# attiny85_jig.net
KiCad netlist of a schematic drawn in EAGLE
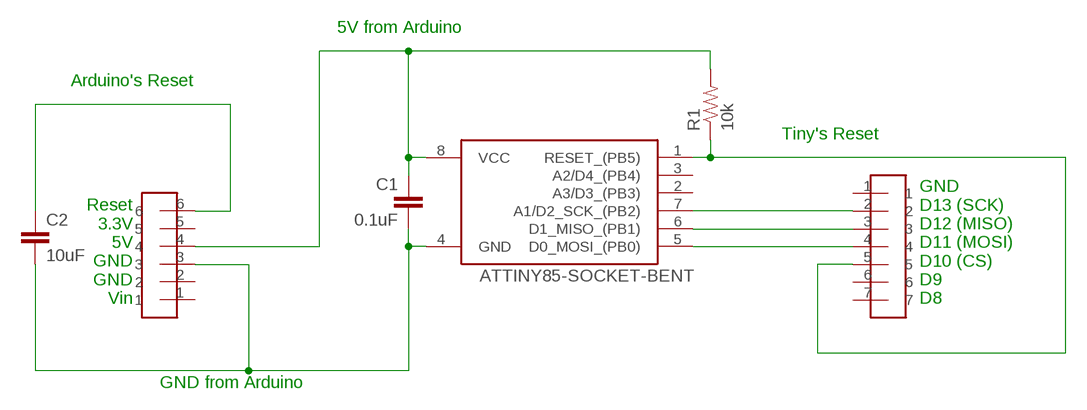
[diagram p0: schematic, sheet 1]

(export (version "E")
  (design (tool "Eeschema 10.0.6"))
  (components
    (comp (ref "C1")
      (value "0.1uF")
      (footprint "eagle-import:0805")
      (libsource (lib "eagle-import") (part "CAP-0805"))
    )
    (comp (ref "C2")
      (value "10uF")
      (footprint "eagle-import:0805")
      (libsource (lib "eagle-import") (part "CAP-0805"))
    )
    (comp (ref "R1")
      (value "10k")
      (footprint "eagle-import:0805")
      (libsource (lib "eagle-import") (part "RESISTOR-0805"))
    )
    (comp (ref "U$1")
      (value "ATTINY85-SOCKET-BENT")
      (footprint "eagle-import:SOCKET-8PIN-BENT")
      (libsource (lib "eagle-import") (part "ATTINY85-SOCKET-BENT"))
    )
    (comp (ref "U$2")
      (value "HEADER-6")
      (footprint "eagle-import:HEADER-6")
      (libsource (lib "eagle-import") (part "HEADER-6"))
    )
    (comp (ref "U$3")
      (value "HEADER-7")
      (footprint "eagle-import:HEADER-7")
      (libsource (lib "eagle-import") (part "HEADER-7"))
    )
  )
  (nets
    (net (code "1") (name "Net-(C2-Pad1)") (class "Default")
      (node (ref "C2") (pin "1") (pinfunction "1_1") (pintype "passive"))
      (node (ref "U$2") (pin "6") (pinfunction "6_6") (pintype "bidirectional"))
    )
    (net (code "2") (name "Net-(U$1-A1{slash}D2_SCK_(PB2))") (class "Default")
      (node (ref "U$1") (pin "7") (pinfunction "A1/D2_SCK_(PB2)_7") (pintype "bidirectional"))
      (node (ref "U$3") (pin "2") (pinfunction "2_2") (pintype "bidirectional"))
    )
    (net (code "3") (name "Net-(U$1-D0_MOSI_(PB0))") (class "Default")
      (node (ref "U$1") (pin "5") (pinfunction "D0_MOSI_(PB0)_5") (pintype "bidirectional"))
      (node (ref "U$3") (pin "4") (pinfunction "4_4") (pintype "bidirectional"))
    )
    (net (code "4") (name "Net-(U$1-D1_MISO_(PB1))") (class "Default")
      (node (ref "U$1") (pin "6") (pinfunction "D1_MISO_(PB1)_6") (pintype "bidirectional"))
      (node (ref "U$3") (pin "3") (pinfunction "3_3") (pintype "bidirectional"))
    )
    (net (code "5") (name "Net-(U$1-GND)") (class "Default")
      (node (ref "C1") (pin "2") (pinfunction "2_2") (pintype "passive"))
      (node (ref "C2") (pin "2") (pinfunction "2_2") (pintype "passive"))
      (node (ref "U$1") (pin "4") (pinfunction "GND_4") (pintype "power_in"))
      (node (ref "U$2") (pin "3") (pinfunction "3_3") (pintype "bidirectional"))
    )
    (net (code "6") (name "Net-(U$1-RESET_(PB5))") (class "Default")
      (node (ref "R1") (pin "1") (pinfunction "1_1") (pintype "passive"))
      (node (ref "U$1") (pin "1") (pinfunction "RESET_(PB5)_1") (pintype "bidirectional"))
      (node (ref "U$3") (pin "5") (pinfunction "5_5") (pintype "bidirectional"))
    )
    (net (code "7") (name "Net-(U$1-VCC)") (class "Default")
      (node (ref "C1") (pin "1") (pinfunction "1_1") (pintype "passive"))
      (node (ref "R1") (pin "2") (pinfunction "2_2") (pintype "passive"))
      (node (ref "U$1") (pin "8") (pinfunction "VCC_8") (pintype "power_in"))
      (node (ref "U$2") (pin "4") (pinfunction "4_4") (pintype "bidirectional"))
    )
    (net (code "8") (name "unconnected-(U$1-A2{slash}D4_(PB4)-Pad3)") (class "Default")
      (node (ref "U$1") (pin "3") (pinfunction "A2/D4_(PB4)_3") (pintype "bidirectional"))
    )
    (net (code "9") (name "unconnected-(U$1-A3{slash}D3_(PB3)-Pad2)") (class "Default")
      (node (ref "U$1") (pin "2") (pinfunction "A3/D3_(PB3)_2") (pintype "bidirectional"))
    )
    (net (code "10") (name "unconnected-(U$2-Pad1)") (class "Default")
      (node (ref "U$2") (pin "1") (pinfunction "1_1") (pintype "bidirectional"))
    )
    (net (code "11") (name "unconnected-(U$2-Pad2)") (class "Default")
      (node (ref "U$2") (pin "2") (pinfunction "2_2") (pintype "bidirectional"))
    )
    (net (code "12") (name "unconnected-(U$2-Pad5)") (class "Default")
      (node (ref "U$2") (pin "5") (pinfunction "5_5") (pintype "bidirectional"))
    )
    (net (code "13") (name "unconnected-(U$3-Pad1)") (class "Default")
      (node (ref "U$3") (pin "1") (pinfunction "1_1") (pintype "bidirectional"))
    )
    (net (code "14") (name "unconnected-(U$3-Pad6)") (class "Default")
      (node (ref "U$3") (pin "6") (pinfunction "6_6") (pintype "bidirectional"))
    )
    (net (code "15") (name "unconnected-(U$3-Pad7)") (class "Default")
      (node (ref "U$3") (pin "7") (pinfunction "7_7") (pintype "bidirectional"))
    )
  )
)
